# Sheet_1_2022-11-14.net
KiCad netlist of a schematic drawn in Altium Designer
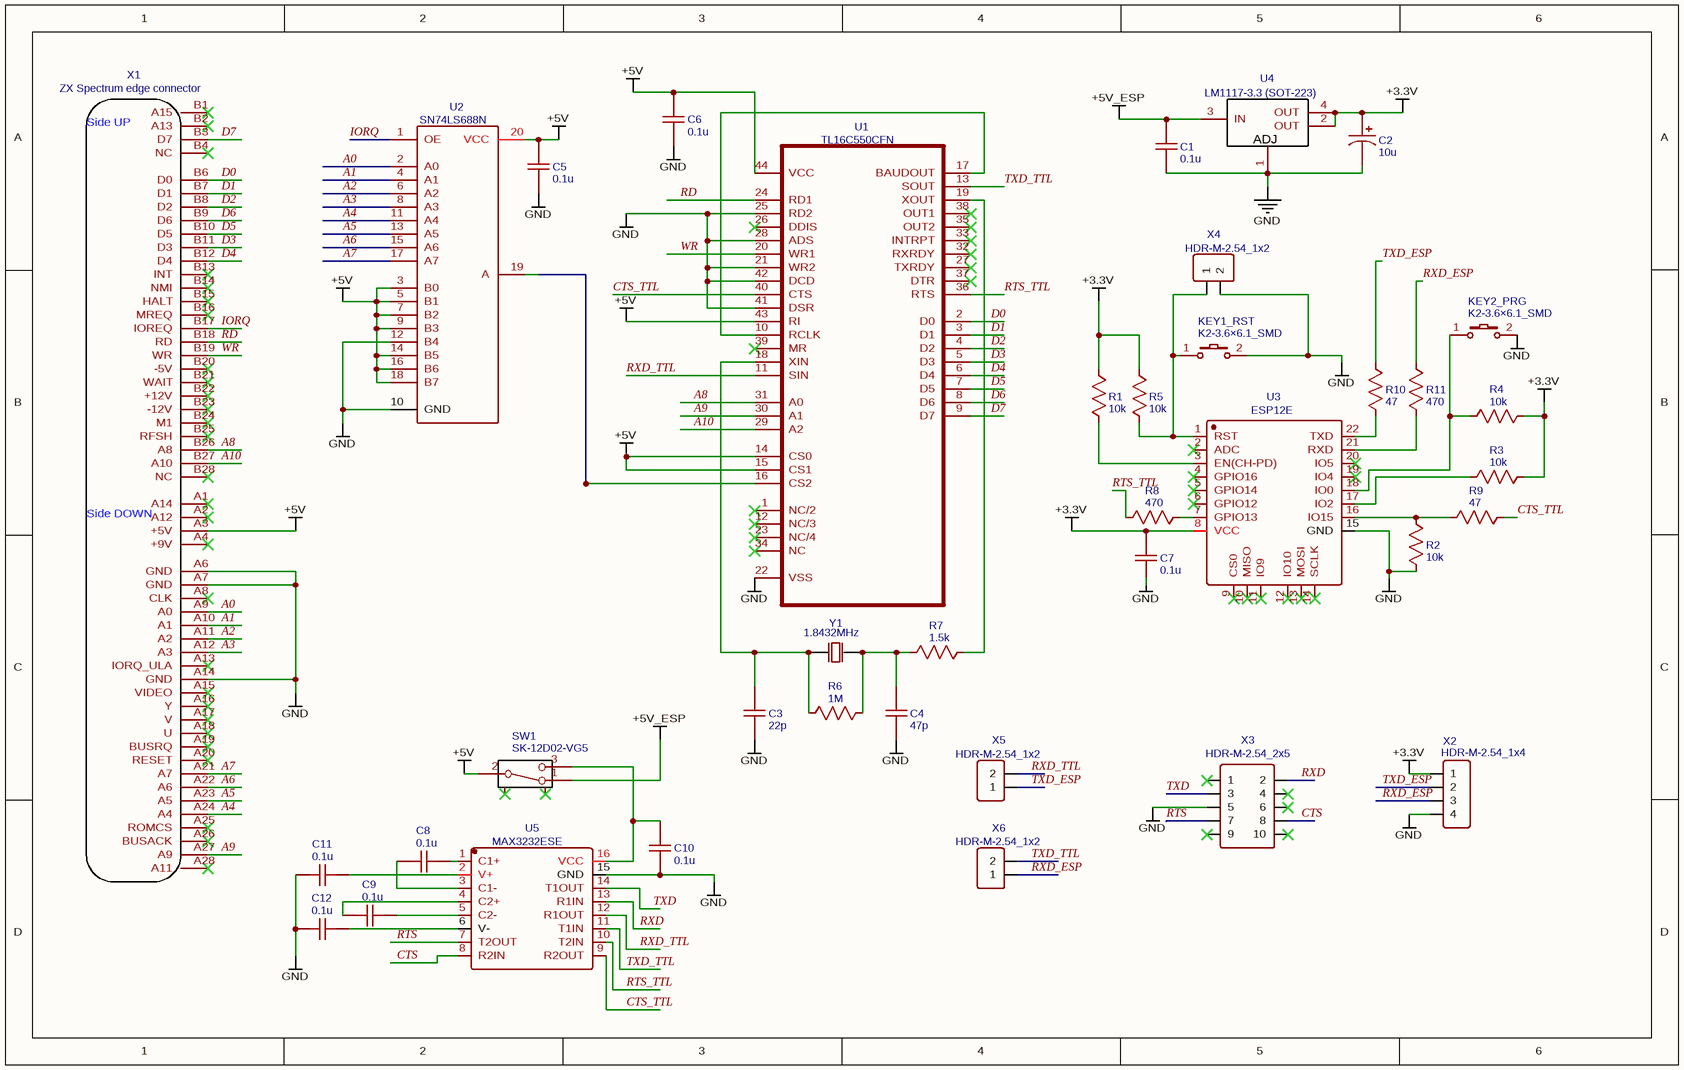
[diagram p0: Sheet_1_2022-11-14.schdoc]

(export (version "E")
  (design (tool "Eeschema 10.0.6"))
  (components
    (comp (ref "C1")
      (value "0.1u")
      (footprint "C0805")
      (fields (field (name "CONTRIBUTOR") "LCEDA_Lib"))
      (libsource (lib "altium-import") (part "root_1_0.1u_"))
    )
    (comp (ref "C2")
      (value "10u")
      (footprint "CASE-A_3216")
      (fields (field (name "CONTRIBUTOR") "LCEDA_Lib"))
      (libsource (lib "altium-import") (part "root_3_10u_"))
    )
    (comp (ref "C3")
      (value "22p")
      (footprint "C0805")
      (fields (field (name "CONTRIBUTOR") "LCEDA_Lib"))
      (libsource (lib "altium-import") (part "root_1_22p_"))
    )
    (comp (ref "C4")
      (value "47p")
      (footprint "C0805")
      (fields (field (name "CONTRIBUTOR") "LCEDA_Lib"))
      (libsource (lib "altium-import") (part "root_1_47p_"))
    )
    (comp (ref "C5")
      (value "0.1u")
      (footprint "C0805")
      (fields (field (name "CONTRIBUTOR") "LCEDA_Lib"))
      (libsource (lib "altium-import") (part "root_1_0.1u_"))
    )
    (comp (ref "C6")
      (value "0.1u")
      (footprint "C0805")
      (fields (field (name "CONTRIBUTOR") "LCEDA_Lib"))
      (libsource (lib "altium-import") (part "root_1_0.1u_"))
    )
    (comp (ref "C7")
      (value "0.1u")
      (footprint "C0805")
      (fields (field (name "CONTRIBUTOR") "LCEDA_Lib"))
      (libsource (lib "altium-import") (part "root_1_0.1u_"))
    )
    (comp (ref "C8")
      (value "0.1u")
      (footprint "C0805")
      (fields (field (name "CONTRIBUTOR") "LCEDA_Lib"))
      (libsource (lib "altium-import") (part "root_2_0.1u_"))
    )
    (comp (ref "C9")
      (value "0.1u")
      (footprint "C0805")
      (fields (field (name "CONTRIBUTOR") "LCEDA_Lib"))
      (libsource (lib "altium-import") (part "root_2_0.1u_"))
    )
    (comp (ref "C10")
      (value "0.1u")
      (footprint "C0805")
      (fields (field (name "CONTRIBUTOR") "LCEDA_Lib"))
      (libsource (lib "altium-import") (part "root_1_0.1u_"))
    )
    (comp (ref "C11")
      (value "0.1u")
      (footprint "C0805")
      (fields (field (name "CONTRIBUTOR") "LCEDA_Lib"))
      (libsource (lib "altium-import") (part "root_2_0.1u_"))
    )
    (comp (ref "C12")
      (value "0.1u")
      (footprint "C0805")
      (fields (field (name "CONTRIBUTOR") "LCEDA_Lib"))
      (libsource (lib "altium-import") (part "root_2_0.1u_"))
    )
    (comp (ref "KEY1_RST")
      (value "K2-3.6×6.1_SMD")
      (footprint "KEY-SMD_2P-L6.2-W3.6-LS8.0")
      (fields
        (field (name "BOM_SUPPLIER PART") "C118141")
        (field (name "BOM_MANUFACTURER PART") "K2-1107ST-A4SW-06")
        (field (name "CONTRIBUTOR") "LCEDA_Lib")
      )
      (libsource (lib "altium-import") (part "root_0_K2-3.6×6.1_SMD_"))
    )
    (comp (ref "KEY2_PRG")
      (value "K2-3.6×6.1_SMD")
      (footprint "KEY-SMD_2P-L6.2-W3.6-LS8.0")
      (fields
        (field (name "BOM_SUPPLIER PART") "C118141")
        (field (name "BOM_MANUFACTURER PART") "K2-1107ST-A4SW-06")
        (field (name "CONTRIBUTOR") "LCEDA_Lib")
      )
      (libsource (lib "altium-import") (part "root_0_K2-3.6×6.1_SMD_"))
    )
    (comp (ref "R1")
      (value "10k")
      (footprint "R0805")
      (fields (field (name "CONTRIBUTOR") "LCEDA_Lib"))
      (libsource (lib "altium-import") (part "root_1_10k_"))
    )
    (comp (ref "R2")
      (value "10k")
      (footprint "R0805")
      (fields (field (name "CONTRIBUTOR") "LCEDA_Lib"))
      (libsource (lib "altium-import") (part "root_1_10k_"))
    )
    (comp (ref "R3")
      (value "10k")
      (footprint "R0805")
      (fields (field (name "CONTRIBUTOR") "LCEDA_Lib"))
      (libsource (lib "altium-import") (part "root_2_10k_"))
    )
    (comp (ref "R4")
      (value "10k")
      (footprint "R0805")
      (fields (field (name "CONTRIBUTOR") "LCEDA_Lib"))
      (libsource (lib "altium-import") (part "root_2_10k_"))
    )
    (comp (ref "R5")
      (value "10k")
      (footprint "R0805")
      (fields (field (name "CONTRIBUTOR") "LCEDA_Lib"))
      (libsource (lib "altium-import") (part "root_1_10k_"))
    )
    (comp (ref "R6")
      (value "1M")
      (footprint "R0805")
      (fields (field (name "CONTRIBUTOR") "LCEDA_Lib"))
      (libsource (lib "altium-import") (part "root_0_1M_"))
    )
    (comp (ref "R7")
      (value "1.5k")
      (footprint "R0805")
      (fields (field (name "CONTRIBUTOR") "LCEDA_Lib"))
      (libsource (lib "altium-import") (part "root_0_1.5k_"))
    )
    (comp (ref "R8")
      (value "470")
      (footprint "R0805")
      (fields (field (name "CONTRIBUTOR") "LCEDA_Lib"))
      (libsource (lib "altium-import") (part "root_2_470_"))
    )
    (comp (ref "R9")
      (value "47")
      (footprint "R0805")
      (fields (field (name "CONTRIBUTOR") "LCEDA_Lib"))
      (libsource (lib "altium-import") (part "root_2_47_"))
    )
    (comp (ref "R10")
      (value "47")
      (footprint "R0805")
      (fields (field (name "CONTRIBUTOR") "LCEDA_Lib"))
      (libsource (lib "altium-import") (part "root_1_47_"))
    )
    (comp (ref "R11")
      (value "470")
      (footprint "R0805")
      (fields (field (name "CONTRIBUTOR") "LCEDA_Lib"))
      (libsource (lib "altium-import") (part "root_1_470_"))
    )
    (comp (ref "SW1")
      (value "SK-12D02-VG5")
      (footprint "SW-TH_SK-12D02VG3")
      (fields (field (name "BOM_SUPPLIER PART") "C136722") (field (name "CONTRIBUTOR") "LCSC"))
      (libsource (lib "altium-import") (part "root_0_SK-12D02-VG5_"))
    )
    (comp (ref "U1")
      (value "TL16C550CFN")
      (footprint "PLCC-44")
      (libsource (lib "altium-import") (part "root_0_TL16C550CFN_"))
    )
    (comp (ref "U2")
      (value "SN74LS688N")
      (footprint "DIP20")
      (libsource (lib "altium-import") (part "root_0_SN74LS688N_"))
    )
    (comp (ref "U3")
      (value "ESP12E")
      (footprint "ESP12E/F")
      (fields (field (name "CONTRIBUTOR") "cpu76239"))
      (libsource (lib "altium-import") (part "root_0_ESP12E_"))
    )
    (comp (ref "U4")
      (value "LM1117-3.3 (SOT-223)")
      (footprint "SOT-223-3_L6.5-W3.4-P2.30-LS7.0-BR")
      (fields
        (field (name "BOM_MANUFACTURER PART") "LM317G-AA3-R")
        (field (name "BOM_SUPPLIER PART") "C19651")
        (field (name "CONTRIBUTOR") "LCEDA_Lib")
      )
      (libsource (lib "altium-import") (part "root_0_LM1117-3.3 (SOT-223)_"))
    )
    (comp (ref "U5")
      (value "MAX3232ESE")
      (footprint "SOP-16_L9.9-W3.9-P1.27-LS6.0-BL")
      (fields (field (name "BOM_SUPPLIER PART") "C2904738") (field (name "CONTRIBUTOR") "LCSC"))
      (libsource (lib "altium-import") (part "root_0_MAX3232ESE_"))
    )
    (comp (ref "X1")
      (value "ZX SPECTRUM CONNECTOR")
      (footprint "ZX SPECTRUM CONNECTOR")
      (fields (field (name "CONTRIBUTOR") "cliff1024"))
      (libsource (lib "altium-import") (part "root_0_ZX SPECTRUM CONNECTOR_"))
    )
    (comp (ref "X2")
      (value "HDR-M-2.54_1x4")
      (footprint "HDR-M-2.54_1X4")
      (fields (field (name "BOM_SUPPLIER PART") "C124378") (field (name "CONTRIBUTOR") "LCEDA_Lib"))
      (libsource (lib "altium-import") (part "root_0_HDR-M-2.54_1x4_"))
    )
    (comp (ref "X3")
      (value "HDR-M-2.54_2x5")
      (footprint "HDR-M-2.54_2X5")
      (fields (field (name "BOM_SUPPLIER PART") "C178292") (field (name "CONTRIBUTOR") "LCEDA_Lib"))
      (libsource (lib "altium-import") (part "root_0_HDR-M-2.54_2x5_"))
    )
    (comp (ref "X4")
      (value "HDR-M-2.54_1x2")
      (footprint "HDR-M-2.54_1X2")
      (fields (field (name "BOM_SUPPLIER PART") "C124375") (field (name "CONTRIBUTOR") "LCEDA_Lib"))
      (libsource (lib "altium-import") (part "root_1_HDR-M-2.54_1x2_"))
    )
    (comp (ref "X5")
      (value "HDR-M-2.54_1x2")
      (footprint "HDR-M-2.54_1X2")
      (fields (field (name "BOM_SUPPLIER PART") "C124375") (field (name "CONTRIBUTOR") "LCEDA_Lib"))
      (libsource (lib "altium-import") (part "root_2_HDR-M-2.54_1x2_"))
    )
    (comp (ref "X6")
      (value "HDR-M-2.54_1x2")
      (footprint "HDR-M-2.54_1X2")
      (fields (field (name "BOM_SUPPLIER PART") "C124375") (field (name "CONTRIBUTOR") "LCEDA_Lib"))
      (libsource (lib "altium-import") (part "root_2_HDR-M-2.54_1x2_"))
    )
    (comp (ref "Y1")
      (value "1.8432MHz")
      (footprint "OSC-TH_L10.0-W4.5-P5.00")
      (fields
        (field (name "BOM_MANUFACTURER PART") "X49UD3579MSD2SC")
        (field (name "BOM_SUPPLIER PART") "C36564")
      )
      (libsource (lib "altium-import") (part "root_0_1.8432MHz_"))
    )
  )
  (nets
    (net (code "1") (name "+3.3V") (class "Default")
      (node (ref "C2") (pin "1") (pinfunction "1_1") (pintype "passive"))
      (node (ref "C7") (pin "2") (pinfunction "2_2") (pintype "passive"))
      (node (ref "R1") (pin "2") (pinfunction "2_2") (pintype "passive"))
      (node (ref "R3") (pin "1") (pinfunction "1_1") (pintype "passive"))
      (node (ref "R4") (pin "1") (pinfunction "1_1") (pintype "passive"))
      (node (ref "R5") (pin "2") (pinfunction "2_2") (pintype "passive"))
      (node (ref "U3") (pin "8") (pinfunction "VCC_8") (pintype "passive"))
      (node (ref "U4") (pin "2") (pinfunction "OUT_2") (pintype "passive"))
      (node (ref "U4") (pin "4") (pinfunction "OUT_4") (pintype "passive"))
      (node (ref "X2") (pin "1") (pinfunction "1_1") (pintype "passive"))
    )
    (net (code "2") (name "+5V") (class "Default")
      (node (ref "C5") (pin "2") (pinfunction "2_2") (pintype "passive"))
      (node (ref "C6") (pin "2") (pinfunction "2_2") (pintype "passive"))
      (node (ref "SW1") (pin "2") (pinfunction "2_2") (pintype "passive"))
      (node (ref "U1") (pin "14") (pinfunction "CS0_14") (pintype "passive"))
      (node (ref "U1") (pin "15") (pinfunction "CS1_15") (pintype "passive"))
      (node (ref "U1") (pin "43") (pinfunction "RI_43") (pintype "passive"))
      (node (ref "U1") (pin "44") (pinfunction "VCC_44") (pintype "passive"))
      (node (ref "U2") (pin "14") (pinfunction "B5_14") (pintype "passive"))
      (node (ref "U2") (pin "16") (pinfunction "B6_16") (pintype "passive"))
      (node (ref "U2") (pin "18") (pinfunction "B7_18") (pintype "passive"))
      (node (ref "U2") (pin "20") (pinfunction "VCC_20") (pintype "passive"))
      (node (ref "U2") (pin "3") (pinfunction "B0_3") (pintype "passive"))
      (node (ref "U2") (pin "5") (pinfunction "B1_5") (pintype "passive"))
      (node (ref "U2") (pin "7") (pinfunction "B2_7") (pintype "passive"))
      (node (ref "U2") (pin "9") (pinfunction "B3_9") (pintype "passive"))
      (node (ref "X1") (pin "A3") (pinfunction "+5V_A3") (pintype "passive"))
    )
    (net (code "3") (name "+5V_ESP") (class "Default")
      (node (ref "C1") (pin "2") (pinfunction "2_2") (pintype "passive"))
      (node (ref "SW1") (pin "1") (pinfunction "1_1") (pintype "passive"))
      (node (ref "U4") (pin "3") (pinfunction "IN_3") (pintype "passive"))
    )
    (net (code "4") (name "/A0") (class "Default")
      (node (ref "U2") (pin "2") (pinfunction "A0_2") (pintype "passive"))
      (node (ref "X1") (pin "A9") (pinfunction "A0_A9") (pintype "passive"))
    )
    (net (code "5") (name "/A1") (class "Default")
      (node (ref "U2") (pin "4") (pinfunction "A1_4") (pintype "passive"))
      (node (ref "X1") (pin "A10") (pinfunction "A1_A10") (pintype "passive"))
    )
    (net (code "6") (name "/A2") (class "Default")
      (node (ref "U2") (pin "6") (pinfunction "A2_6") (pintype "passive"))
      (node (ref "X1") (pin "A11") (pinfunction "A2_A11") (pintype "passive"))
    )
    (net (code "7") (name "/A3") (class "Default")
      (node (ref "U2") (pin "8") (pinfunction "A3_8") (pintype "passive"))
      (node (ref "X1") (pin "A12") (pinfunction "A3_A12") (pintype "passive"))
    )
    (net (code "8") (name "/A4") (class "Default")
      (node (ref "U2") (pin "11") (pinfunction "A4_11") (pintype "passive"))
      (node (ref "X1") (pin "A24") (pinfunction "A4_A24") (pintype "passive"))
    )
    (net (code "9") (name "/A5") (class "Default")
      (node (ref "U2") (pin "13") (pinfunction "A5_13") (pintype "passive"))
      (node (ref "X1") (pin "A23") (pinfunction "A5_A23") (pintype "passive"))
    )
    (net (code "10") (name "/A6") (class "Default")
      (node (ref "U2") (pin "15") (pinfunction "A6_15") (pintype "passive"))
      (node (ref "X1") (pin "A22") (pinfunction "A6_A22") (pintype "passive"))
    )
    (net (code "11") (name "/A7") (class "Default")
      (node (ref "U2") (pin "17") (pinfunction "A7_17") (pintype "passive"))
      (node (ref "X1") (pin "A21") (pinfunction "A7_A21") (pintype "passive"))
    )
    (net (code "12") (name "/A8") (class "Default")
      (node (ref "U1") (pin "31") (pinfunction "A0_31") (pintype "passive"))
      (node (ref "X1") (pin "B26") (pinfunction "A8_B26") (pintype "passive"))
    )
    (net (code "13") (name "/A9") (class "Default")
      (node (ref "U1") (pin "30") (pinfunction "A1_30") (pintype "passive"))
      (node (ref "X1") (pin "A27") (pinfunction "A9_A27") (pintype "passive"))
    )
    (net (code "14") (name "/A10") (class "Default")
      (node (ref "U1") (pin "29") (pinfunction "A2_29") (pintype "passive"))
      (node (ref "X1") (pin "B27") (pinfunction "A10_B27") (pintype "passive"))
    )
    (net (code "15") (name "/CTS") (class "Default")
      (node (ref "U5") (pin "8") (pinfunction "R2IN_8") (pintype "passive"))
      (node (ref "X3") (pin "8") (pinfunction "8_8") (pintype "passive"))
    )
    (net (code "16") (name "/CTS_TTL") (class "Default")
      (node (ref "R9") (pin "1") (pinfunction "1_1") (pintype "passive"))
      (node (ref "U1") (pin "40") (pinfunction "CTS_40") (pintype "passive"))
      (node (ref "U5") (pin "9") (pinfunction "R2OUT_9") (pintype "passive"))
    )
    (net (code "17") (name "/D0") (class "Default")
      (node (ref "U1") (pin "2") (pinfunction "D0_2") (pintype "passive"))
      (node (ref "X1") (pin "B6") (pinfunction "D0_B6") (pintype "passive"))
    )
    (net (code "18") (name "/D1") (class "Default")
      (node (ref "U1") (pin "3") (pinfunction "D1_3") (pintype "passive"))
      (node (ref "X1") (pin "B7") (pinfunction "D1_B7") (pintype "passive"))
    )
    (net (code "19") (name "/D2") (class "Default")
      (node (ref "U1") (pin "4") (pinfunction "D2_4") (pintype "passive"))
      (node (ref "X1") (pin "B8") (pinfunction "D2_B8") (pintype "passive"))
    )
    (net (code "20") (name "/D3") (class "Default")
      (node (ref "U1") (pin "5") (pinfunction "D3_5") (pintype "passive"))
      (node (ref "X1") (pin "B11") (pinfunction "D3_B11") (pintype "passive"))
    )
    (net (code "21") (name "/D4") (class "Default")
      (node (ref "U1") (pin "6") (pinfunction "D4_6") (pintype "passive"))
      (node (ref "X1") (pin "B12") (pinfunction "D4_B12") (pintype "passive"))
    )
    (net (code "22") (name "/D5") (class "Default")
      (node (ref "U1") (pin "7") (pinfunction "D5_7") (pintype "passive"))
      (node (ref "X1") (pin "B10") (pinfunction "D5_B10") (pintype "passive"))
    )
    (net (code "23") (name "/D6") (class "Default")
      (node (ref "U1") (pin "8") (pinfunction "D6_8") (pintype "passive"))
      (node (ref "X1") (pin "B9") (pinfunction "D6_B9") (pintype "passive"))
    )
    (net (code "24") (name "/D7") (class "Default")
      (node (ref "U1") (pin "9") (pinfunction "D7_9") (pintype "passive"))
      (node (ref "X1") (pin "B3") (pinfunction "D7_B3") (pintype "passive"))
    )
    (net (code "25") (name "/IORQ") (class "Default")
      (node (ref "U2") (pin "1") (pinfunction "OE_1") (pintype "passive"))
      (node (ref "X1") (pin "B17") (pinfunction "IOREQ_B17") (pintype "passive"))
    )
    (net (code "26") (name "/RD") (class "Default")
      (node (ref "U1") (pin "24") (pinfunction "RD1_24") (pintype "passive"))
      (node (ref "X1") (pin "B18") (pinfunction "RD_B18") (pintype "passive"))
    )
    (net (code "27") (name "/RTS") (class "Default")
      (node (ref "U5") (pin "7") (pinfunction "T2OUT_7") (pintype "passive"))
      (node (ref "X3") (pin "7") (pinfunction "7_7") (pintype "passive"))
    )
    (net (code "28") (name "/RTS_TTL") (class "Default")
      (node (ref "R8") (pin "2") (pinfunction "2_2") (pintype "passive"))
      (node (ref "U1") (pin "36") (pinfunction "RTS_36") (pintype "passive"))
      (node (ref "U5") (pin "10") (pinfunction "T2IN_10") (pintype "passive"))
    )
    (net (code "29") (name "/RXD") (class "Default")
      (node (ref "U5") (pin "13") (pinfunction "R1IN_13") (pintype "passive"))
      (node (ref "X3") (pin "2") (pinfunction "2_2") (pintype "passive"))
    )
    (net (code "30") (name "/RXD_ESP") (class "Default")
      (node (ref "R11") (pin "2") (pinfunction "2_2") (pintype "passive"))
      (node (ref "X2") (pin "3") (pinfunction "3_3") (pintype "passive"))
      (node (ref "X6") (pin "1") (pinfunction "1_1") (pintype "passive"))
    )
    (net (code "31") (name "/RXD_TTL") (class "Default")
      (node (ref "U1") (pin "11") (pinfunction "SIN_11") (pintype "passive"))
      (node (ref "U5") (pin "12") (pinfunction "R1OUT_12") (pintype "passive"))
      (node (ref "X5") (pin "2") (pinfunction "2_2") (pintype "passive"))
    )
    (net (code "32") (name "/TXD") (class "Default")
      (node (ref "U5") (pin "14") (pinfunction "T1OUT_14") (pintype "passive"))
      (node (ref "X3") (pin "3") (pinfunction "3_3") (pintype "passive"))
    )
    (net (code "33") (name "/TXD_ESP") (class "Default")
      (node (ref "R10") (pin "2") (pinfunction "2_2") (pintype "passive"))
      (node (ref "X2") (pin "2") (pinfunction "2_2") (pintype "passive"))
      (node (ref "X5") (pin "1") (pinfunction "1_1") (pintype "passive"))
    )
    (net (code "34") (name "/TXD_TTL") (class "Default")
      (node (ref "U1") (pin "13") (pinfunction "SOUT_13") (pintype "passive"))
      (node (ref "U5") (pin "11") (pinfunction "T1IN_11") (pintype "passive"))
      (node (ref "X6") (pin "2") (pinfunction "2_2") (pintype "passive"))
    )
    (net (code "35") (name "/WR") (class "Default")
      (node (ref "U1") (pin "20") (pinfunction "WR1_20") (pintype "passive"))
      (node (ref "X1") (pin "B19") (pinfunction "WR_B19") (pintype "passive"))
    )
    (net (code "36") (name "GND") (class "Default")
      (node (ref "C1") (pin "1") (pinfunction "1_1") (pintype "passive"))
      (node (ref "C10") (pin "1") (pinfunction "1_1") (pintype "passive"))
      (node (ref "C11") (pin "2") (pinfunction "2_2") (pintype "passive"))
      (node (ref "C12") (pin "2") (pinfunction "2_2") (pintype "passive"))
      (node (ref "C2") (pin "2") (pinfunction "2_2") (pintype "passive"))
      (node (ref "C3") (pin "1") (pinfunction "1_1") (pintype "passive"))
      (node (ref "C4") (pin "1") (pinfunction "1_1") (pintype "passive"))
      (node (ref "C5") (pin "1") (pinfunction "1_1") (pintype "passive"))
      (node (ref "C6") (pin "1") (pinfunction "1_1") (pintype "passive"))
      (node (ref "C7") (pin "1") (pinfunction "1_1") (pintype "passive"))
      (node (ref "KEY1_RST") (pin "2") (pinfunction "2_2") (pintype "passive"))
      (node (ref "KEY2_PRG") (pin "2") (pinfunction "2_2") (pintype "passive"))
      (node (ref "R2") (pin "1") (pinfunction "1_1") (pintype "passive"))
      (node (ref "U1") (pin "21") (pinfunction "WR2_21") (pintype "passive"))
      (node (ref "U1") (pin "22") (pinfunction "VSS_22") (pintype "passive"))
      (node (ref "U1") (pin "25") (pinfunction "RD2_25") (pintype "passive"))
      (node (ref "U1") (pin "28") (pinfunction "ADS_28") (pintype "passive"))
      (node (ref "U1") (pin "41") (pinfunction "DSR_41") (pintype "passive"))
      (node (ref "U1") (pin "42") (pinfunction "DCD_42") (pintype "passive"))
      (node (ref "U2") (pin "10") (pinfunction "GND_10") (pintype "passive"))
      (node (ref "U2") (pin "12") (pinfunction "B4_12") (pintype "passive"))
      (node (ref "U3") (pin "15") (pinfunction "GND_15") (pintype "passive"))
      (node (ref "U4") (pin "1") (pinfunction "ADJ_1") (pintype "passive"))
      (node (ref "U5") (pin "15") (pinfunction "GND_15") (pintype "passive"))
      (node (ref "X1") (pin "A14") (pinfunction "GND_A14") (pintype "passive"))
      (node (ref "X1") (pin "A6") (pinfunction "GND_A6") (pintype "passive"))
      (node (ref "X1") (pin "A7") (pinfunction "GND_A7") (pintype "passive"))
      (node (ref "X2") (pin "4") (pinfunction "4_4") (pintype "passive"))
      (node (ref "X3") (pin "5") (pinfunction "5_5") (pintype "passive"))
      (node (ref "X4") (pin "2") (pinfunction "2_2") (pintype "passive"))
    )
    (net (code "37") (name "Net-(U1-BAUDOUT)") (class "Default")
      (node (ref "U1") (pin "10") (pinfunction "RCLK_10") (pintype "passive"))
      (node (ref "U1") (pin "17") (pinfunction "BAUDOUT_17") (pintype "passive"))
    )
    (net (code "38") (name "Net-(U1-CS2)") (class "Default")
      (node (ref "U1") (pin "16") (pinfunction "CS2_16") (pintype "passive"))
      (node (ref "U2") (pin "19") (pinfunction "A_19") (pintype "passive"))
    )
    (net (code "39") (name "Net-(U1-XIN)") (class "Default")
      (node (ref "C3") (pin "2") (pinfunction "2_2") (pintype "passive"))
      (node (ref "R6") (pin "1") (pinfunction "1_1") (pintype "passive"))
      (node (ref "U1") (pin "18") (pinfunction "XIN_18") (pintype "passive"))
      (node (ref "Y1") (pin "2") (pinfunction "OSC2_2") (pintype "passive"))
    )
    (net (code "40") (name "Net-(U1-XOUT)") (class "Default")
      (node (ref "R7") (pin "2") (pinfunction "2_2") (pintype "passive"))
      (node (ref "U1") (pin "19") (pinfunction "XOUT_19") (pintype "passive"))
    )
    (net (code "41") (name "Net-(U3-EN(CH-PD))") (class "Default")
      (node (ref "R1") (pin "1") (pinfunction "1_1") (pintype "passive"))
      (node (ref "U3") (pin "3") (pinfunction "EN(CH-PD)_3") (pintype "passive"))
    )
    (net (code "42") (name "Net-(U3-GPIO13)") (class "Default")
      (node (ref "R8") (pin "1") (pinfunction "1_1") (pintype "passive"))
      (node (ref "U3") (pin "7") (pinfunction "GPIO13_7") (pintype "passive"))
    )
    (net (code "43") (name "Net-(U3-IO0)") (class "Default")
      (node (ref "KEY2_PRG") (pin "1") (pinfunction "1_1") (pintype "passive"))
      (node (ref "R4") (pin "2") (pinfunction "2_2") (pintype "passive"))
      (node (ref "U3") (pin "18") (pinfunction "IO0_18") (pintype "passive"))
    )
    (net (code "44") (name "Net-(U3-IO2)") (class "Default")
      (node (ref "R3") (pin "2") (pinfunction "2_2") (pintype "passive"))
      (node (ref "U3") (pin "17") (pinfunction "IO2_17") (pintype "passive"))
    )
    (net (code "45") (name "Net-(U3-IO15)") (class "Default")
      (node (ref "R2") (pin "2") (pinfunction "2_2") (pintype "passive"))
      (node (ref "R9") (pin "2") (pinfunction "2_2") (pintype "passive"))
      (node (ref "U3") (pin "16") (pinfunction "IO15_16") (pintype "passive"))
    )
    (net (code "46") (name "Net-(U3-RST)") (class "Default")
      (node (ref "KEY1_RST") (pin "1") (pinfunction "1_1") (pintype "passive"))
      (node (ref "R5") (pin "1") (pinfunction "1_1") (pintype "passive"))
      (node (ref "U3") (pin "1") (pinfunction "RST_1") (pintype "passive"))
      (node (ref "X4") (pin "1") (pinfunction "1_1") (pintype "passive"))
    )
    (net (code "47") (name "Net-(U3-RXD)") (class "Default")
      (node (ref "R11") (pin "1") (pinfunction "1_1") (pintype "passive"))
      (node (ref "U3") (pin "21") (pinfunction "RXD_21") (pintype "passive"))
    )
    (net (code "48") (name "Net-(U3-TXD)") (class "Default")
      (node (ref "R10") (pin "1") (pinfunction "1_1") (pintype "passive"))
      (node (ref "U3") (pin "22") (pinfunction "TXD_22") (pintype "passive"))
    )
    (net (code "49") (name "Net-(U5-C1+)") (class "Default")
      (node (ref "C8") (pin "1") (pinfunction "1_1") (pintype "passive"))
      (node (ref "U5") (pin "1") (pinfunction "C1+_1") (pintype "passive"))
    )
    (net (code "50") (name "Net-(U5-C1-)") (class "Default")
      (node (ref "C8") (pin "2") (pinfunction "2_2") (pintype "passive"))
      (node (ref "U5") (pin "3") (pinfunction "C1-_3") (pintype "passive"))
    )
    (net (code "51") (name "Net-(U5-C2+)") (class "Default")
      (node (ref "C9") (pin "2") (pinfunction "2_2") (pintype "passive"))
      (node (ref "U5") (pin "4") (pinfunction "C2+_4") (pintype "passive"))
    )
    (net (code "52") (name "Net-(U5-C2-)") (class "Default")
      (node (ref "C9") (pin "1") (pinfunction "1_1") (pintype "passive"))
      (node (ref "U5") (pin "5") (pinfunction "C2-_5") (pintype "passive"))
    )
    (net (code "53") (name "Net-(U5-V+)") (class "Default")
      (node (ref "C11") (pin "1") (pinfunction "1_1") (pintype "passive"))
      (node (ref "U5") (pin "2") (pinfunction "V+_2") (pintype "passive"))
    )
    (net (code "54") (name "Net-(U5-V-)") (class "Default")
      (node (ref "C12") (pin "1") (pinfunction "1_1") (pintype "passive"))
      (node (ref "U5") (pin "6") (pinfunction "V-_6") (pintype "passive"))
    )
    (net (code "55") (name "Net-(U5-VCC)") (class "Default")
      (node (ref "C10") (pin "2") (pinfunction "2_2") (pintype "passive"))
      (node (ref "SW1") (pin "3") (pinfunction "3_3") (pintype "passive"))
      (node (ref "U5") (pin "16") (pinfunction "VCC_16") (pintype "passive"))
    )
    (net (code "56") (name "Net-(Y1-OSC1)") (class "Default")
      (node (ref "C4") (pin "2") (pinfunction "2_2") (pintype "passive"))
      (node (ref "R6") (pin "2") (pinfunction "2_2") (pintype "passive"))
      (node (ref "R7") (pin "1") (pinfunction "1_1") (pintype "passive"))
      (node (ref "Y1") (pin "1") (pinfunction "OSC1_1") (pintype "passive"))
    )
    (net (code "57") (name "unconnected-(SW1-Pad4)") (class "Default")
      (node (ref "SW1") (pin "4") (pinfunction "4_4") (pintype "passive+no_connect"))
    )
    (net (code "58") (name "unconnected-(SW1-Pad5)") (class "Default")
      (node (ref "SW1") (pin "5") (pinfunction "5_5") (pintype "passive+no_connect"))
    )
    (net (code "59") (name "unconnected-(U1-DDIS-Pad26)") (class "Default")
      (node (ref "U1") (pin "26") (pinfunction "DDIS_26") (pintype "passive+no_connect"))
    )
    (net (code "60") (name "unconnected-(U1-DTR-Pad37)") (class "Default")
      (node (ref "U1") (pin "37") (pinfunction "DTR_37") (pintype "passive+no_connect"))
    )
    (net (code "61") (name "unconnected-(U1-INTRPT-Pad33)") (class "Default")
      (node (ref "U1") (pin "33") (pinfunction "INTRPT_33") (pintype "passive+no_connect"))
    )
    (net (code "62") (name "unconnected-(U1-MR-Pad39)") (class "Default")
      (node (ref "U1") (pin "39") (pinfunction "MR_39") (pintype "passive+no_connect"))
    )
    (net (code "63") (name "unconnected-(U1-NC-Pad34)") (class "Default")
      (node (ref "U1") (pin "34") (pinfunction "NC_34") (pintype "passive+no_connect"))
    )
    (net (code "64") (name "unconnected-(U1-NC{slash}2-Pad1)") (class "Default")
      (node (ref "U1") (pin "1") (pinfunction "NC/2_1") (pintype "passive+no_connect"))
    )
    (net (code "65") (name "unconnected-(U1-NC{slash}3-Pad12)") (class "Default")
      (node (ref "U1") (pin "12") (pinfunction "NC/3_12") (pintype "passive+no_connect"))
    )
    (net (code "66") (name "unconnected-(U1-NC{slash}4-Pad23)") (class "Default")
      (node (ref "U1") (pin "23") (pinfunction "NC/4_23") (pintype "passive+no_connect"))
    )
    (net (code "67") (name "unconnected-(U1-OUT1-Pad38)") (class "Default")
      (node (ref "U1") (pin "38") (pinfunction "OUT1_38") (pintype "passive+no_connect"))
    )
    (net (code "68") (name "unconnected-(U1-OUT2-Pad35)") (class "Default")
      (node (ref "U1") (pin "35") (pinfunction "OUT2_35") (pintype "passive+no_connect"))
    )
    (net (code "69") (name "unconnected-(U1-RXRDY-Pad32)") (class "Default")
      (node (ref "U1") (pin "32") (pinfunction "RXRDY_32") (pintype "passive+no_connect"))
    )
    (net (code "70") (name "unconnected-(U1-TXRDY-Pad27)") (class "Default")
      (node (ref "U1") (pin "27") (pinfunction "TXRDY_27") (pintype "passive+no_connect"))
    )
    (net (code "71") (name "unconnected-(U3-ADC-Pad2)") (class "Default")
      (node (ref "U3") (pin "2") (pinfunction "ADC_2") (pintype "passive+no_connect"))
    )
    (net (code "72") (name "unconnected-(U3-CS0-Pad9)") (class "Default")
      (node (ref "U3") (pin "9") (pinfunction "CS0_9") (pintype "passive+no_connect"))
    )
    (net (code "73") (name "unconnected-(U3-GPIO12-Pad6)") (class "Default")
      (node (ref "U3") (pin "6") (pinfunction "GPIO12_6") (pintype "passive+no_connect"))
    )
    (net (code "74") (name "unconnected-(U3-GPIO14-Pad5)") (class "Default")
      (node (ref "U3") (pin "5") (pinfunction "GPIO14_5") (pintype "passive+no_connect"))
    )
    (net (code "75") (name "unconnected-(U3-GPIO16-Pad4)") (class "Default")
      (node (ref "U3") (pin "4") (pinfunction "GPIO16_4") (pintype "passive+no_connect"))
    )
    (net (code "76") (name "unconnected-(U3-IO4-Pad19)") (class "Default")
      (node (ref "U3") (pin "19") (pinfunction "IO4_19") (pintype "passive+no_connect"))
    )
    (net (code "77") (name "unconnected-(U3-IO5-Pad20)") (class "Default")
      (node (ref "U3") (pin "20") (pinfunction "IO5_20") (pintype "passive+no_connect"))
    )
    (net (code "78") (name "unconnected-(U3-IO9-Pad11)") (class "Default")
      (node (ref "U3") (pin "11") (pinfunction "IO9_11") (pintype "passive+no_connect"))
    )
    (net (code "79") (name "unconnected-(U3-IO10-Pad12)") (class "Default")
      (node (ref "U3") (pin "12") (pinfunction "IO10_12") (pintype "passive+no_connect"))
    )
    (net (code "80") (name "unconnected-(U3-MISO-Pad10)") (class "Default")
      (node (ref "U3") (pin "10") (pinfunction "MISO_10") (pintype "passive+no_connect"))
    )
    (net (code "81") (name "unconnected-(U3-MOSI-Pad13)") (class "Default")
      (node (ref "U3") (pin "13") (pinfunction "MOSI_13") (pintype "passive+no_connect"))
    )
    (net (code "82") (name "unconnected-(U3-SCLK-Pad14)") (class "Default")
      (node (ref "U3") (pin "14") (pinfunction "SCLK_14") (pintype "passive+no_connect"))
    )
    (net (code "83") (name "unconnected-(X1-+9V-PadA4)") (class "Default")
      (node (ref "X1") (pin "A4") (pinfunction "+9V_A4") (pintype "passive+no_connect"))
    )
    (net (code "84") (name "unconnected-(X1-+12V-PadB22)") (class "Default")
      (node (ref "X1") (pin "B22") (pinfunction "+12V_B22") (pintype "passive+no_connect"))
    )
    (net (code "85") (name "unconnected-(X1--5V-PadB20)") (class "Default")
      (node (ref "X1") (pin "B20") (pinfunction "-5V_B20") (pintype "passive+no_connect"))
    )
    (net (code "86") (name "unconnected-(X1--12V-PadB23)") (class "Default")
      (node (ref "X1") (pin "B23") (pinfunction "-12V_B23") (pintype "passive+no_connect"))
    )
    (net (code "87") (name "unconnected-(X1-A11-PadA28)") (class "Default")
      (node (ref "X1") (pin "A28") (pinfunction "A11_A28") (pintype "passive+no_connect"))
    )
    (net (code "88") (name "unconnected-(X1-A12-PadA2)") (class "Default")
      (node (ref "X1") (pin "A2") (pinfunction "A12_A2") (pintype "passive+no_connect"))
    )
    (net (code "89") (name "unconnected-(X1-A13-PadB2)") (class "Default")
      (node (ref "X1") (pin "B2") (pinfunction "A13_B2") (pintype "passive+no_connect"))
    )
    (net (code "90") (name "unconnected-(X1-A14-PadA1)") (class "Default")
      (node (ref "X1") (pin "A1") (pinfunction "A14_A1") (pintype "passive+no_connect"))
    )
    (net (code "91") (name "unconnected-(X1-A15-PadB1)") (class "Default")
      (node (ref "X1") (pin "B1") (pinfunction "A15_B1") (pintype "passive+no_connect"))
    )
    (net (code "92") (name "unconnected-(X1-BUSACK-PadA26)") (class "Default")
      (node (ref "X1") (pin "A26") (pinfunction "BUSACK_A26") (pintype "passive+no_connect"))
    )
    (net (code "93") (name "unconnected-(X1-BUSRQ-PadA19)") (class "Default")
      (node (ref "X1") (pin "A19") (pinfunction "BUSRQ_A19") (pintype "passive+no_connect"))
    )
    (net (code "94") (name "unconnected-(X1-CLK-PadA8)") (class "Default")
      (node (ref "X1") (pin "A8") (pinfunction "CLK_A8") (pintype "passive+no_connect"))
    )
    (net (code "95") (name "unconnected-(X1-HALT-PadB15)") (class "Default")
      (node (ref "X1") (pin "B15") (pinfunction "HALT_B15") (pintype "passive+no_connect"))
    )
    (net (code "96") (name "unconnected-(X1-INT-PadB13)") (class "Default")
      (node (ref "X1") (pin "B13") (pinfunction "INT_B13") (pintype "passive+no_connect"))
    )
    (net (code "97") (name "unconnected-(X1-IORQ_ULA-PadA13)") (class "Default")
      (node (ref "X1") (pin "A13") (pinfunction "IORQ_ULA_A13") (pintype "passive+no_connect"))
    )
    (net (code "98") (name "unconnected-(X1-M1-PadB24)") (class "Default")
      (node (ref "X1") (pin "B24") (pinfunction "M1_B24") (pintype "passive+no_connect"))
    )
    (net (code "99") (name "unconnected-(X1-MREQ-PadB16)") (class "Default")
      (node (ref "X1") (pin "B16") (pinfunction "MREQ_B16") (pintype "passive+no_connect"))
    )
    (net (code "100") (name "unconnected-(X1-NC-PadB4)") (class "Default")
      (node (ref "X1") (pin "B4") (pinfunction "NC_B4") (pintype "passive+no_connect"))
    )
    (net (code "101") (name "unconnected-(X1-NC-PadB28)") (class "Default")
      (node (ref "X1") (pin "B28") (pinfunction "NC_B28") (pintype "passive+no_connect"))
    )
    (net (code "102") (name "unconnected-(X1-NMI-PadB14)") (class "Default")
      (node (ref "X1") (pin "B14") (pinfunction "NMI_B14") (pintype "passive+no_connect"))
    )
    (net (code "103") (name "unconnected-(X1-RESET-PadA20)") (class "Default")
      (node (ref "X1") (pin "A20") (pinfunction "RESET_A20") (pintype "passive+no_connect"))
    )
    (net (code "104") (name "unconnected-(X1-RFSH-PadB25)") (class "Default")
      (node (ref "X1") (pin "B25") (pinfunction "RFSH_B25") (pintype "passive+no_connect"))
    )
    (net (code "105") (name "unconnected-(X1-ROMCS-PadA25)") (class "Default")
      (node (ref "X1") (pin "A25") (pinfunction "ROMCS_A25") (pintype "passive+no_connect"))
    )
    (net (code "106") (name "unconnected-(X1-U-PadA18)") (class "Default")
      (node (ref "X1") (pin "A18") (pinfunction "U_A18") (pintype "passive+no_connect"))
    )
    (net (code "107") (name "unconnected-(X1-V-PadA17)") (class "Default")
      (node (ref "X1") (pin "A17") (pinfunction "V_A17") (pintype "passive+no_connect"))
    )
    (net (code "108") (name "unconnected-(X1-VIDEO-PadA15)") (class "Default")
      (node (ref "X1") (pin "A15") (pinfunction "VIDEO_A15") (pintype "passive+no_connect"))
    )
    (net (code "109") (name "unconnected-(X1-WAIT-PadB21)") (class "Default")
      (node (ref "X1") (pin "B21") (pinfunction "WAIT_B21") (pintype "passive+no_connect"))
    )
    (net (code "110") (name "unconnected-(X1-Y-PadA16)") (class "Default")
      (node (ref "X1") (pin "A16") (pinfunction "Y_A16") (pintype "passive+no_connect"))
    )
    (net (code "111") (name "unconnected-(X3-Pad1)") (class "Default")
      (node (ref "X3") (pin "1") (pinfunction "1_1") (pintype "passive+no_connect"))
    )
    (net (code "112") (name "unconnected-(X3-Pad4)") (class "Default")
      (node (ref "X3") (pin "4") (pinfunction "4_4") (pintype "passive+no_connect"))
    )
    (net (code "113") (name "unconnected-(X3-Pad6)") (class "Default")
      (node (ref "X3") (pin "6") (pinfunction "6_6") (pintype "passive+no_connect"))
    )
    (net (code "114") (name "unconnected-(X3-Pad9)") (class "Default")
      (node (ref "X3") (pin "9") (pinfunction "9_9") (pintype "passive+no_connect"))
    )
    (net (code "115") (name "unconnected-(X3-Pad10)") (class "Default")
      (node (ref "X3") (pin "10") (pinfunction "10_10") (pintype "passive+no_connect"))
    )
  )
)
